# GBxCart_RW_Mini_v1_0_Schematic.net
KiCad netlist of a schematic drawn in EAGLE
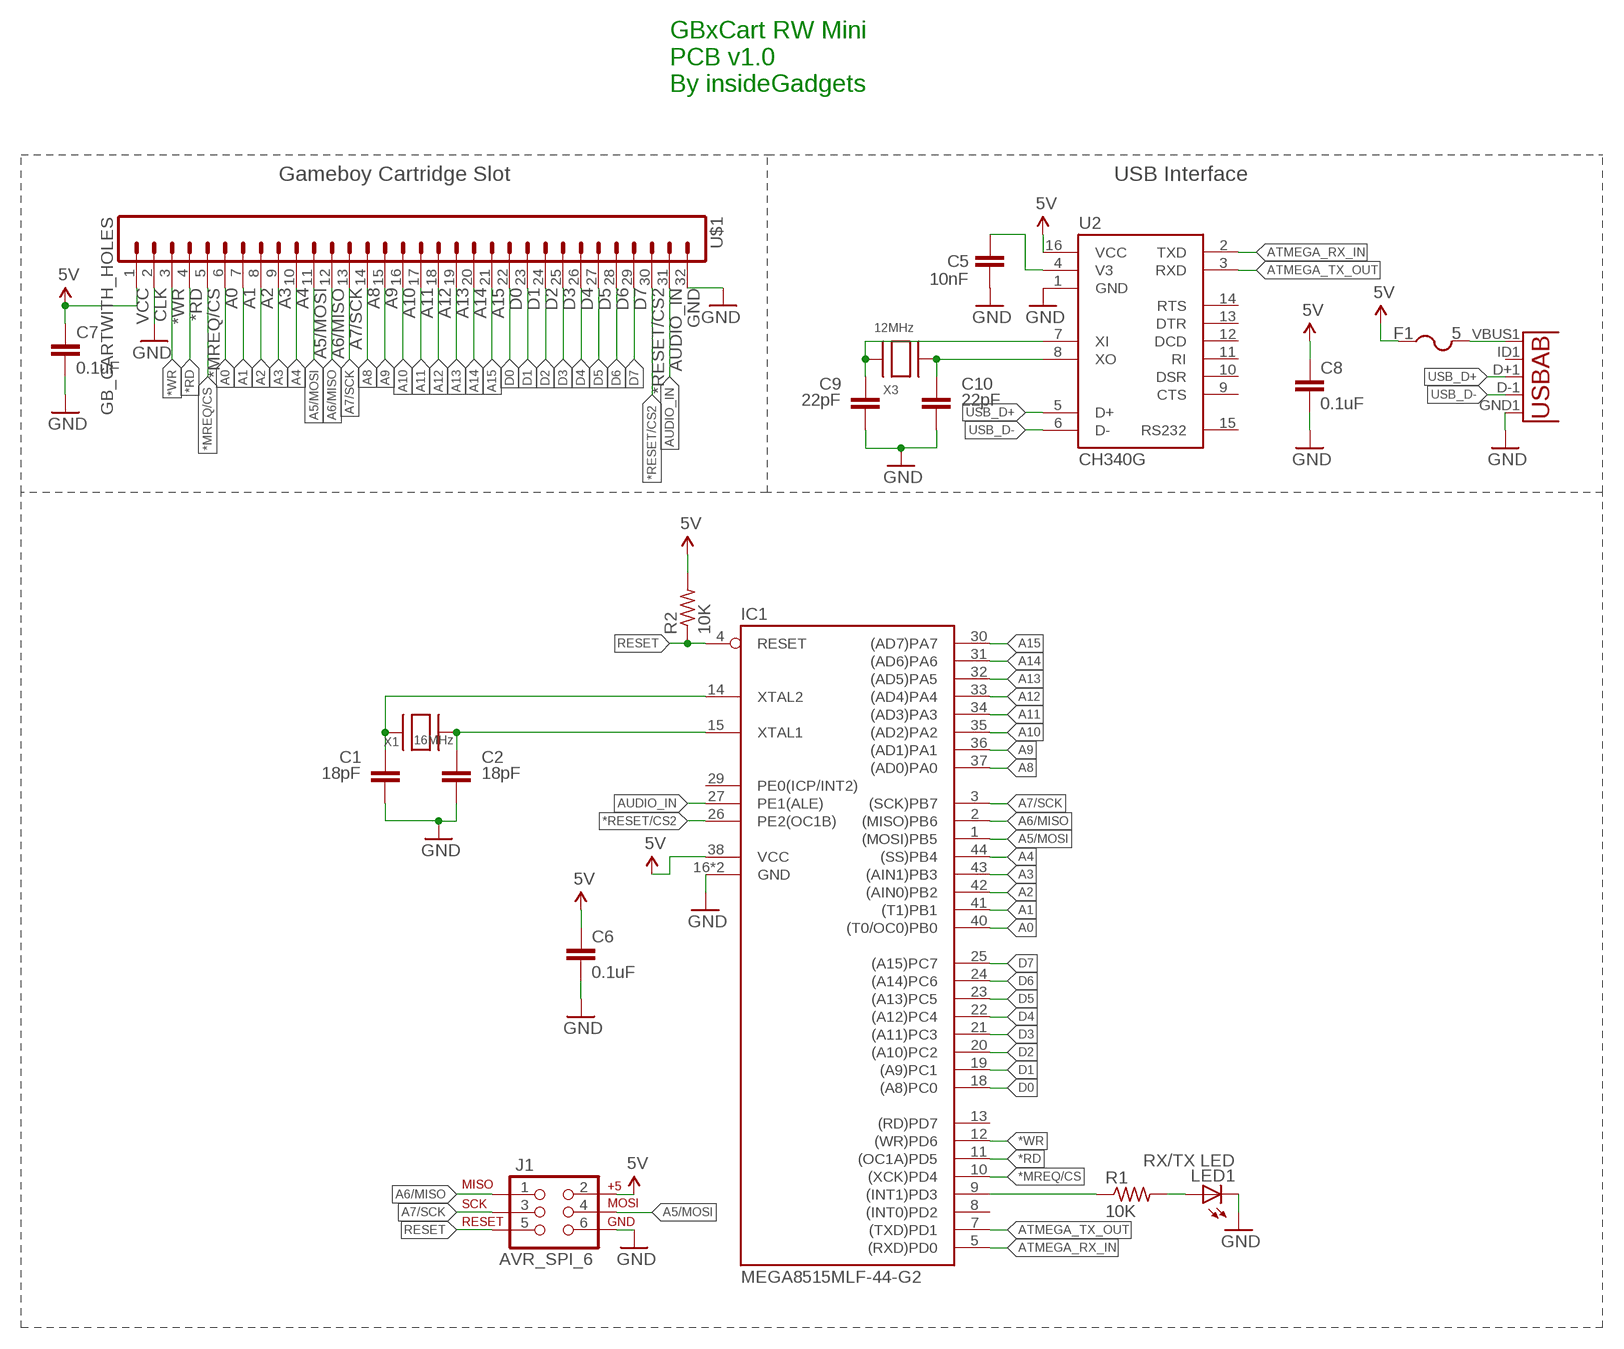
[diagram p0: schematic, sheet 1]

(export (version "E")
  (design (tool "Eeschema 10.0.6"))
  (components
    (comp (ref "C1")
      (value "18pF")
      (footprint "eagle-import:C0603K")
      (libsource (lib "eagle-import") (part "CAP0603"))
    )
    (comp (ref "C2")
      (value "18pF")
      (footprint "eagle-import:C0603K")
      (libsource (lib "eagle-import") (part "CAP0603"))
    )
    (comp (ref "C5")
      (value "10nF")
      (footprint "eagle-import:C0805K")
      (libsource (lib "eagle-import") (part "CAP0805"))
    )
    (comp (ref "C6")
      (value "0.1uF")
      (footprint "eagle-import:C0603K")
      (libsource (lib "eagle-import") (part "CAP0603"))
    )
    (comp (ref "C7")
      (value "0.1uF")
      (footprint "eagle-import:C0805K")
      (libsource (lib "eagle-import") (part "CAP0805"))
    )
    (comp (ref "C8")
      (value "0.1uF")
      (footprint "eagle-import:C0805K")
      (libsource (lib "eagle-import") (part "CAP0805"))
    )
    (comp (ref "C9")
      (value "22pF")
      (footprint "eagle-import:C0805K")
      (libsource (lib "eagle-import") (part "CAP0805"))
    )
    (comp (ref "C10")
      (value "22pF")
      (footprint "eagle-import:C0805K")
      (libsource (lib "eagle-import") (part "CAP0805"))
    )
    (comp (ref "F1")
      (value "5")
      (footprint "eagle-import:R1206")
      (libsource (lib "eagle-import") (part "PTCFUSE-1206"))
    )
    (comp (ref "IC1")
      (value "MEGA8515MLF-44-G2")
      (footprint "eagle-import:MLF-44-G2")
      (libsource (lib "eagle-import") (part "MEGA8515MLF-44-G2"))
    )
    (comp (ref "J1")
      (value "AVR_SPI_6")
      (footprint "eagle-import:2X3_2")
      (libsource (lib "eagle-import") (part "AVR_SPI_PRG_6"))
    )
    (comp (ref "LED1")
      (value "RX/TX LED")
      (footprint "eagle-import:CHIP-LED0805-NS")
      (libsource (lib "eagle-import") (part "LEDCHIP-LED0805-NS"))
    )
    (comp (ref "R1")
      (value "10K")
      (footprint "eagle-import:R0805_2")
      (libsource (lib "eagle-import") (part "R-US_R0805_2"))
    )
    (comp (ref "R2")
      (value "10K")
      (footprint "eagle-import:R0603")
      (libsource (lib "eagle-import") (part "R-US_R0603"))
    )
    (comp (ref "U$1")
      (value "GB_CARTWITH_HOLES")
      (footprint "eagle-import:GB_CART_WHOLES")
      (libsource (lib "eagle-import") (part "GB_CARTWITH_HOLES"))
    )
    (comp (ref "U1")
      (value "USBEP")
      (footprint "eagle-import:USB-MICRO-SMD-EXTRAPADS")
      (libsource (lib "eagle-import") (part "USBEP"))
    )
    (comp (ref "U2")
      (value "CH340G")
      (footprint "eagle-import:SO16")
      (libsource (lib "eagle-import") (part "CH340G"))
    )
    (comp (ref "X1")
      (value "16MHz")
      (footprint "eagle-import:XTAL32-25")
      (libsource (lib "eagle-import") (part "XTAL3.2X2.5"))
    )
    (comp (ref "X3")
      (value "12MHz")
      (footprint "eagle-import:XTAL32-25")
      (libsource (lib "eagle-import") (part "XTAL3.2X2.5"))
    )
  )
  (nets
    (net (code "1") (name "*MREQ{slash}CS") (class "Default")
      (node (ref "IC1") (pin "10") (pinfunction "(XCK)PD4_10") (pintype "bidirectional"))
      (node (ref "U$1") (pin "5") (pinfunction "5_5") (pintype "passive"))
    )
    (net (code "2") (name "*RD") (class "Default")
      (node (ref "IC1") (pin "11") (pinfunction "(OC1A)PD5_11") (pintype "bidirectional"))
      (node (ref "U$1") (pin "4") (pinfunction "4_4") (pintype "passive"))
    )
    (net (code "3") (name "*RESET{slash}CS2") (class "Default")
      (node (ref "IC1") (pin "26") (pinfunction "PE2(OC1B)_26") (pintype "bidirectional"))
      (node (ref "U$1") (pin "30") (pinfunction "30_30") (pintype "passive"))
    )
    (net (code "4") (name "*WR") (class "Default")
      (node (ref "IC1") (pin "12") (pinfunction "(WR)PD6_12") (pintype "bidirectional"))
      (node (ref "U$1") (pin "3") (pinfunction "3_3") (pintype "passive"))
    )
    (net (code "5") (name "5V") (class "Default")
      (node (ref "C6") (pin "1") (pinfunction "1_1") (pintype "passive"))
      (node (ref "C7") (pin "1") (pinfunction "1_1") (pintype "passive"))
      (node (ref "C8") (pin "1") (pinfunction "1_1") (pintype "passive"))
      (node (ref "F1") (pin "1") (pinfunction "1_1") (pintype "passive"))
      (node (ref "IC1") (pin "38") (pinfunction "VCC_38") (pintype "power_in"))
      (node (ref "J1") (pin "2") (pinfunction "2_2") (pintype "passive"))
      (node (ref "R2") (pin "2") (pinfunction "2_2") (pintype "passive"))
      (node (ref "U$1") (pin "1") (pinfunction "1_1") (pintype "passive"))
      (node (ref "U2") (pin "16") (pinfunction "VCC_16") (pintype "power_in"))
    )
    (net (code "6") (name "A0") (class "Default")
      (node (ref "IC1") (pin "40") (pinfunction "(T0/OC0)PB0_40") (pintype "bidirectional"))
      (node (ref "U$1") (pin "6") (pinfunction "6_6") (pintype "passive"))
    )
    (net (code "7") (name "A1") (class "Default")
      (node (ref "IC1") (pin "41") (pinfunction "(T1)PB1_41") (pintype "bidirectional"))
      (node (ref "U$1") (pin "7") (pinfunction "7_7") (pintype "passive"))
    )
    (net (code "8") (name "A2") (class "Default")
      (node (ref "IC1") (pin "42") (pinfunction "(AIN0)PB2_42") (pintype "bidirectional"))
      (node (ref "U$1") (pin "8") (pinfunction "8_8") (pintype "passive"))
    )
    (net (code "9") (name "A3") (class "Default")
      (node (ref "IC1") (pin "43") (pinfunction "(AIN1)PB3_43") (pintype "bidirectional"))
      (node (ref "U$1") (pin "9") (pinfunction "9_9") (pintype "passive"))
    )
    (net (code "10") (name "A4") (class "Default")
      (node (ref "IC1") (pin "44") (pinfunction "(SS)PB4_44") (pintype "bidirectional"))
      (node (ref "U$1") (pin "10") (pinfunction "10_10") (pintype "passive"))
    )
    (net (code "11") (name "A5{slash}MOSI") (class "Default")
      (node (ref "IC1") (pin "1") (pinfunction "(MOSI)PB5_1") (pintype "bidirectional"))
      (node (ref "J1") (pin "4") (pinfunction "4_4") (pintype "passive"))
      (node (ref "U$1") (pin "11") (pinfunction "11_11") (pintype "passive"))
    )
    (net (code "12") (name "A6{slash}MISO") (class "Default")
      (node (ref "IC1") (pin "2") (pinfunction "(MISO)PB6_2") (pintype "bidirectional"))
      (node (ref "J1") (pin "1") (pinfunction "1_1") (pintype "passive"))
      (node (ref "U$1") (pin "12") (pinfunction "12_12") (pintype "passive"))
    )
    (net (code "13") (name "A7{slash}SCK") (class "Default")
      (node (ref "IC1") (pin "3") (pinfunction "(SCK)PB7_3") (pintype "bidirectional"))
      (node (ref "J1") (pin "3") (pinfunction "3_3") (pintype "passive"))
      (node (ref "U$1") (pin "13") (pinfunction "13_13") (pintype "passive"))
    )
    (net (code "14") (name "A8") (class "Default")
      (node (ref "IC1") (pin "37") (pinfunction "(AD0)PA0_37") (pintype "bidirectional"))
      (node (ref "U$1") (pin "14") (pinfunction "14_14") (pintype "passive"))
    )
    (net (code "15") (name "A9") (class "Default")
      (node (ref "IC1") (pin "36") (pinfunction "(AD1)PA1_36") (pintype "bidirectional"))
      (node (ref "U$1") (pin "15") (pinfunction "15_15") (pintype "passive"))
    )
    (net (code "16") (name "A10") (class "Default")
      (node (ref "IC1") (pin "35") (pinfunction "(AD2)PA2_35") (pintype "bidirectional"))
      (node (ref "U$1") (pin "16") (pinfunction "16_16") (pintype "passive"))
    )
    (net (code "17") (name "A11") (class "Default")
      (node (ref "IC1") (pin "34") (pinfunction "(AD3)PA3_34") (pintype "bidirectional"))
      (node (ref "U$1") (pin "17") (pinfunction "17_17") (pintype "passive"))
    )
    (net (code "18") (name "A12") (class "Default")
      (node (ref "IC1") (pin "33") (pinfunction "(AD4)PA4_33") (pintype "bidirectional"))
      (node (ref "U$1") (pin "18") (pinfunction "18_18") (pintype "passive"))
    )
    (net (code "19") (name "A13") (class "Default")
      (node (ref "IC1") (pin "32") (pinfunction "(AD5)PA5_32") (pintype "bidirectional"))
      (node (ref "U$1") (pin "19") (pinfunction "19_19") (pintype "passive"))
    )
    (net (code "20") (name "A14") (class "Default")
      (node (ref "IC1") (pin "31") (pinfunction "(AD6)PA6_31") (pintype "bidirectional"))
      (node (ref "U$1") (pin "20") (pinfunction "20_20") (pintype "passive"))
    )
    (net (code "21") (name "A15") (class "Default")
      (node (ref "IC1") (pin "30") (pinfunction "(AD7)PA7_30") (pintype "bidirectional"))
      (node (ref "U$1") (pin "21") (pinfunction "21_21") (pintype "passive"))
    )
    (net (code "22") (name "ATMEGA_RX_IN") (class "Default")
      (node (ref "IC1") (pin "5") (pinfunction "(RXD)PD0_5") (pintype "bidirectional"))
      (node (ref "U2") (pin "2") (pinfunction "TXD_2") (pintype "bidirectional"))
    )
    (net (code "23") (name "ATMEGA_TX_OUT") (class "Default")
      (node (ref "IC1") (pin "7") (pinfunction "(TXD)PD1_7") (pintype "bidirectional"))
      (node (ref "U2") (pin "3") (pinfunction "RXD_3") (pintype "bidirectional"))
    )
    (net (code "24") (name "AUDIO_IN") (class "Default")
      (node (ref "IC1") (pin "27") (pinfunction "PE1(ALE)_27") (pintype "bidirectional"))
      (node (ref "U$1") (pin "31") (pinfunction "31_31") (pintype "passive"))
    )
    (net (code "25") (name "D0") (class "Default")
      (node (ref "IC1") (pin "18") (pinfunction "(A8)PC0_18") (pintype "bidirectional"))
      (node (ref "U$1") (pin "22") (pinfunction "22_22") (pintype "passive"))
    )
    (net (code "26") (name "D1") (class "Default")
      (node (ref "IC1") (pin "19") (pinfunction "(A9)PC1_19") (pintype "bidirectional"))
      (node (ref "U$1") (pin "23") (pinfunction "23_23") (pintype "passive"))
    )
    (net (code "27") (name "D2") (class "Default")
      (node (ref "IC1") (pin "20") (pinfunction "(A10)PC2_20") (pintype "bidirectional"))
      (node (ref "U$1") (pin "24") (pinfunction "24_24") (pintype "passive"))
    )
    (net (code "28") (name "D3") (class "Default")
      (node (ref "IC1") (pin "21") (pinfunction "(A11)PC3_21") (pintype "bidirectional"))
      (node (ref "U$1") (pin "25") (pinfunction "25_25") (pintype "passive"))
    )
    (net (code "29") (name "D4") (class "Default")
      (node (ref "IC1") (pin "22") (pinfunction "(A12)PC4_22") (pintype "bidirectional"))
      (node (ref "U$1") (pin "26") (pinfunction "26_26") (pintype "passive"))
    )
    (net (code "30") (name "D5") (class "Default")
      (node (ref "IC1") (pin "23") (pinfunction "(A13)PC5_23") (pintype "bidirectional"))
      (node (ref "U$1") (pin "27") (pinfunction "27_27") (pintype "passive"))
    )
    (net (code "31") (name "D6") (class "Default")
      (node (ref "IC1") (pin "24") (pinfunction "(A14)PC6_24") (pintype "bidirectional"))
      (node (ref "U$1") (pin "28") (pinfunction "28_28") (pintype "passive"))
    )
    (net (code "32") (name "D7") (class "Default")
      (node (ref "IC1") (pin "25") (pinfunction "(A15)PC7_25") (pintype "bidirectional"))
      (node (ref "U$1") (pin "29") (pinfunction "29_29") (pintype "passive"))
    )
    (net (code "33") (name "GND") (class "Default")
      (node (ref "C1") (pin "2") (pinfunction "2_2") (pintype "passive"))
      (node (ref "C10") (pin "2") (pinfunction "2_2") (pintype "passive"))
      (node (ref "C2") (pin "2") (pinfunction "2_2") (pintype "passive"))
      (node (ref "C5") (pin "2") (pinfunction "2_2") (pintype "passive"))
      (node (ref "C6") (pin "2") (pinfunction "2_2") (pintype "passive"))
      (node (ref "C7") (pin "2") (pinfunction "2_2") (pintype "passive"))
      (node (ref "C8") (pin "2") (pinfunction "2_2") (pintype "passive"))
      (node (ref "C9") (pin "2") (pinfunction "2_2") (pintype "passive"))
      (node (ref "IC1") (pin "16") (pinfunction "GND_16") (pintype "power_in"))
      (node (ref "IC1") (pin "45") (pinfunction "GND_45") (pintype "power_in"))
      (node (ref "J1") (pin "6") (pinfunction "6_6") (pintype "passive"))
      (node (ref "LED1") (pin "C") (pinfunction "C_C") (pintype "passive"))
      (node (ref "U$1") (pin "2") (pinfunction "2_2") (pintype "passive"))
      (node (ref "U$1") (pin "32") (pinfunction "32_32") (pintype "passive"))
      (node (ref "U1") (pin "GND1") (pinfunction "GND_GND1") (pintype "bidirectional"))
      (node (ref "U2") (pin "1") (pinfunction "GND_1") (pintype "power_in"))
    )
    (net (code "34") (name "Net-(IC1-(INT1)PD3)") (class "Default")
      (node (ref "IC1") (pin "9") (pinfunction "(INT1)PD3_9") (pintype "bidirectional"))
      (node (ref "R1") (pin "1") (pinfunction "1_1") (pintype "passive"))
    )
    (net (code "35") (name "Net-(IC1-XTAL1)") (class "Default")
      (node (ref "C2") (pin "1") (pinfunction "1_1") (pintype "passive"))
      (node (ref "IC1") (pin "15") (pinfunction "XTAL1_15") (pintype "bidirectional"))
      (node (ref "X1") (pin "2") (pinfunction "P$2_2") (pintype "bidirectional"))
    )
    (net (code "36") (name "Net-(IC1-XTAL2)") (class "Default")
      (node (ref "C1") (pin "1") (pinfunction "1_1") (pintype "passive"))
      (node (ref "IC1") (pin "14") (pinfunction "XTAL2_14") (pintype "bidirectional"))
      (node (ref "X1") (pin "1") (pinfunction "P$1_1") (pintype "bidirectional"))
    )
    (net (code "37") (name "Net-(LED1-PadA)") (class "Default")
      (node (ref "LED1") (pin "A") (pinfunction "A_A") (pintype "passive"))
      (node (ref "R1") (pin "2") (pinfunction "2_2") (pintype "passive"))
    )
    (net (code "38") (name "Net-(U1-VBUS)") (class "Default")
      (node (ref "F1") (pin "2") (pinfunction "2_2") (pintype "passive"))
      (node (ref "U1") (pin "VBUS1") (pinfunction "VBUS_VBUS1") (pintype "bidirectional"))
    )
    (net (code "39") (name "Net-(U2-V3)") (class "Default")
      (node (ref "C5") (pin "1") (pinfunction "1_1") (pintype "passive"))
      (node (ref "U2") (pin "4") (pinfunction "V3_4") (pintype "power_in"))
    )
    (net (code "40") (name "Net-(U2-XI)") (class "Default")
      (node (ref "C9") (pin "1") (pinfunction "1_1") (pintype "passive"))
      (node (ref "U2") (pin "7") (pinfunction "XI_7") (pintype "bidirectional"))
      (node (ref "X3") (pin "1") (pinfunction "P$1_1") (pintype "bidirectional"))
    )
    (net (code "41") (name "Net-(U2-XO)") (class "Default")
      (node (ref "C10") (pin "1") (pinfunction "1_1") (pintype "passive"))
      (node (ref "U2") (pin "8") (pinfunction "XO_8") (pintype "bidirectional"))
      (node (ref "X3") (pin "2") (pinfunction "P$2_2") (pintype "bidirectional"))
    )
    (net (code "42") (name "RESET") (class "Default")
      (node (ref "IC1") (pin "4") (pinfunction "RESET_4") (pintype "input"))
      (node (ref "J1") (pin "5") (pinfunction "5_5") (pintype "passive"))
      (node (ref "R2") (pin "1") (pinfunction "1_1") (pintype "passive"))
    )
    (net (code "43") (name "USB_D+") (class "Default")
      (node (ref "U1") (pin "D+1") (pinfunction "D+_D+1") (pintype "bidirectional"))
      (node (ref "U2") (pin "5") (pinfunction "D+_5") (pintype "bidirectional"))
    )
    (net (code "44") (name "USB_D-") (class "Default")
      (node (ref "U1") (pin "D-1") (pinfunction "D-_D-1") (pintype "bidirectional"))
      (node (ref "U2") (pin "6") (pinfunction "D-_6") (pintype "bidirectional"))
    )
    (net (code "45") (name "unconnected-(IC1-(INT0)PD2-Pad8)") (class "Default")
      (node (ref "IC1") (pin "8") (pinfunction "(INT0)PD2_8") (pintype "bidirectional"))
    )
    (net (code "46") (name "unconnected-(IC1-(RD)PD7-Pad13)") (class "Default")
      (node (ref "IC1") (pin "13") (pinfunction "(RD)PD7_13") (pintype "bidirectional"))
    )
    (net (code "47") (name "unconnected-(IC1-NC1-Pad6)") (class "Default")
      (node (ref "IC1") (pin "6") (pinfunction "NC1_6") (pintype "no_connect"))
    )
    (net (code "48") (name "unconnected-(IC1-NC2-Pad17)") (class "Default")
      (node (ref "IC1") (pin "17") (pinfunction "NC2_17") (pintype "no_connect"))
    )
    (net (code "49") (name "unconnected-(IC1-NC3-Pad28)") (class "Default")
      (node (ref "IC1") (pin "28") (pinfunction "NC3_28") (pintype "no_connect"))
    )
    (net (code "50") (name "unconnected-(IC1-NC4-Pad39)") (class "Default")
      (node (ref "IC1") (pin "39") (pinfunction "NC4_39") (pintype "no_connect"))
    )
    (net (code "51") (name "unconnected-(IC1-PE0(ICP{slash}INT2)-Pad29)") (class "Default")
      (node (ref "IC1") (pin "29") (pinfunction "PE0(ICP/INT2)_29") (pintype "bidirectional"))
    )
    (net (code "52") (name "unconnected-(U1-USBID-PadID1)") (class "Default")
      (node (ref "U1") (pin "ID1") (pinfunction "USBID_ID1") (pintype "bidirectional"))
    )
    (net (code "53") (name "unconnected-(U2-CTS-Pad9)") (class "Default")
      (node (ref "U2") (pin "9") (pinfunction "CTS_9") (pintype "bidirectional"))
    )
    (net (code "54") (name "unconnected-(U2-DCD-Pad12)") (class "Default")
      (node (ref "U2") (pin "12") (pinfunction "DCD_12") (pintype "bidirectional"))
    )
    (net (code "55") (name "unconnected-(U2-DSR-Pad10)") (class "Default")
      (node (ref "U2") (pin "10") (pinfunction "DSR_10") (pintype "bidirectional"))
    )
    (net (code "56") (name "unconnected-(U2-DTR-Pad13)") (class "Default")
      (node (ref "U2") (pin "13") (pinfunction "DTR_13") (pintype "bidirectional"))
    )
    (net (code "57") (name "unconnected-(U2-RI-Pad11)") (class "Default")
      (node (ref "U2") (pin "11") (pinfunction "RI_11") (pintype "bidirectional"))
    )
    (net (code "58") (name "unconnected-(U2-RS232-Pad15)") (class "Default")
      (node (ref "U2") (pin "15") (pinfunction "RS232_15") (pintype "bidirectional"))
    )
    (net (code "59") (name "unconnected-(U2-RTS-Pad14)") (class "Default")
      (node (ref "U2") (pin "14") (pinfunction "RTS_14") (pintype "bidirectional"))
    )
  )
)
